# 16.net
KiCad netlist of a schematic drawn in EasyEDA Pro
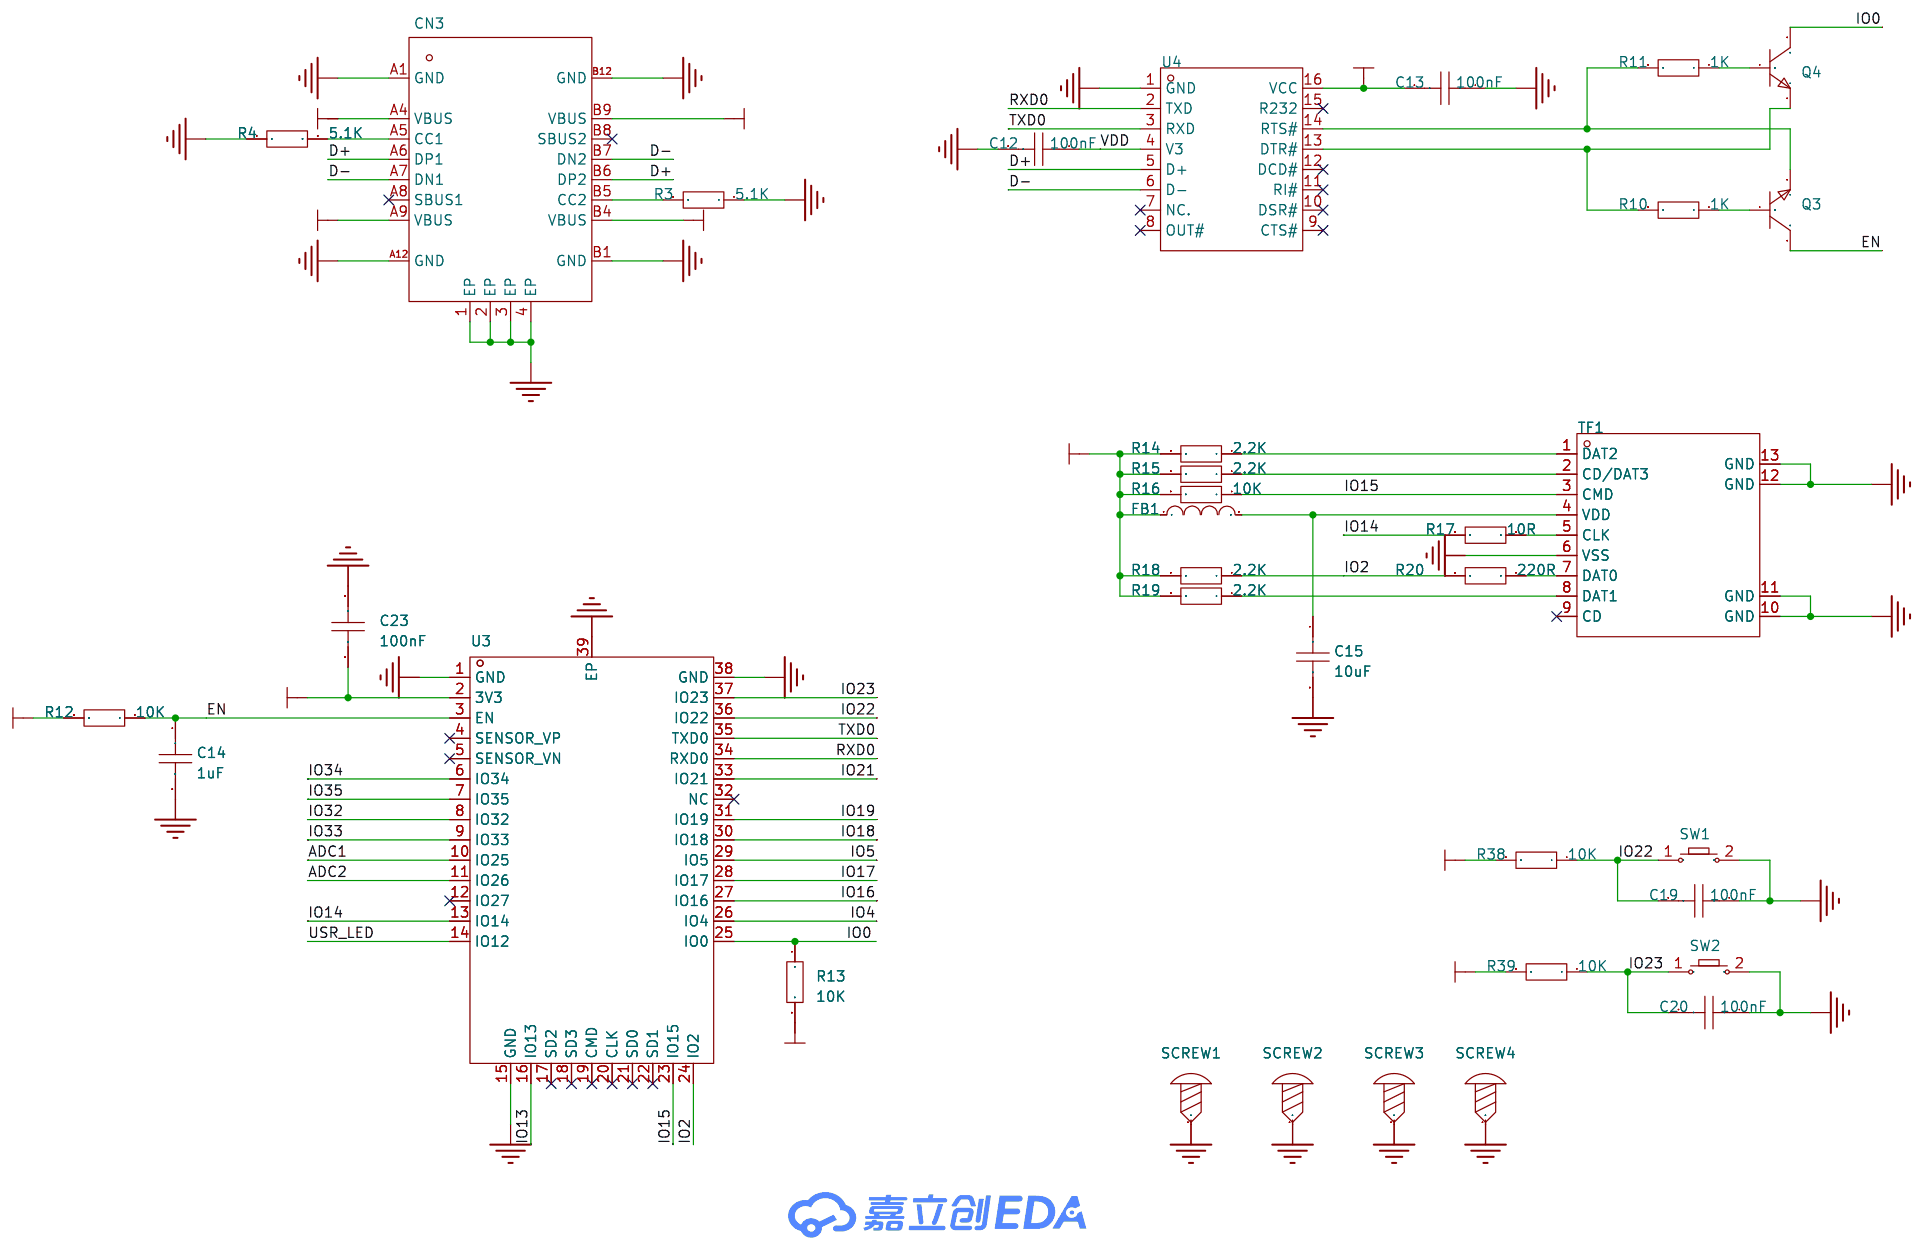
[diagram p0: ESP32]
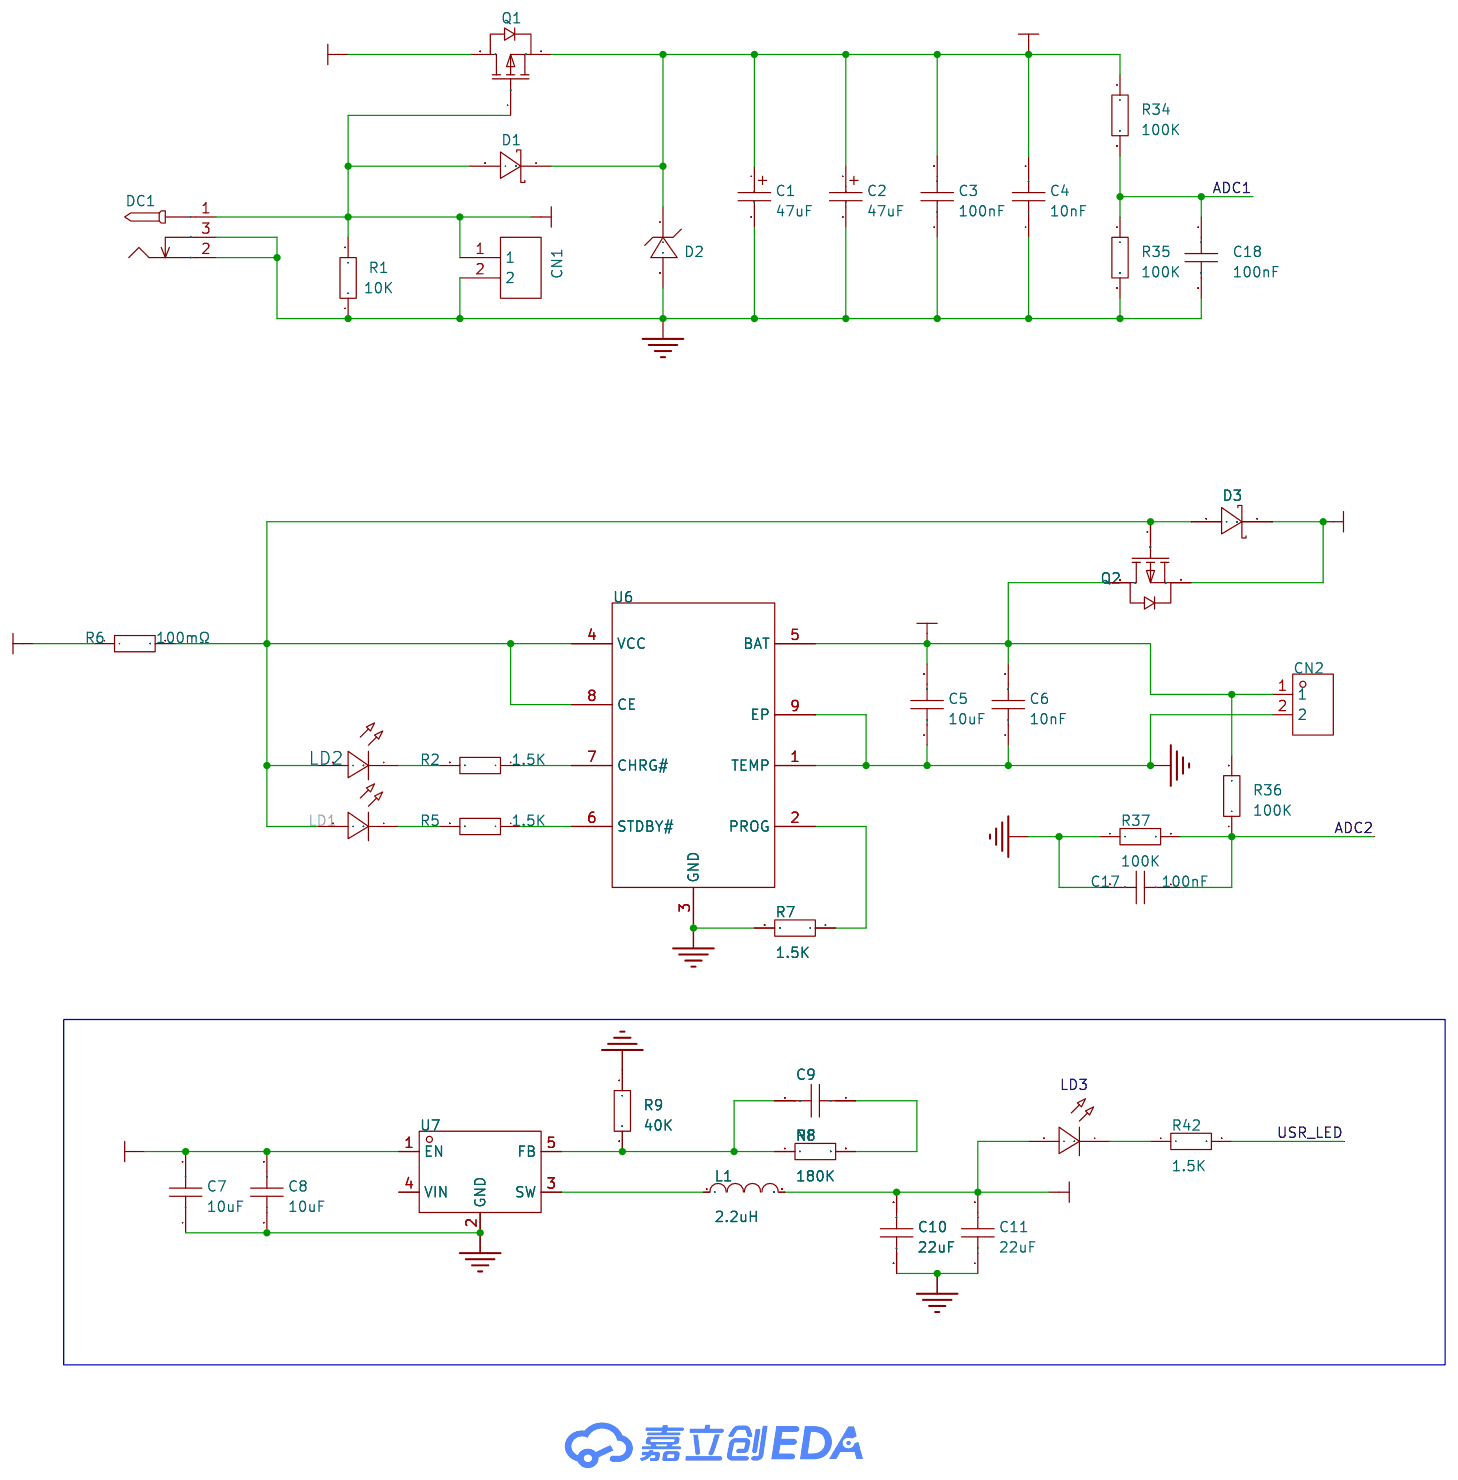
[diagram p1: DC]
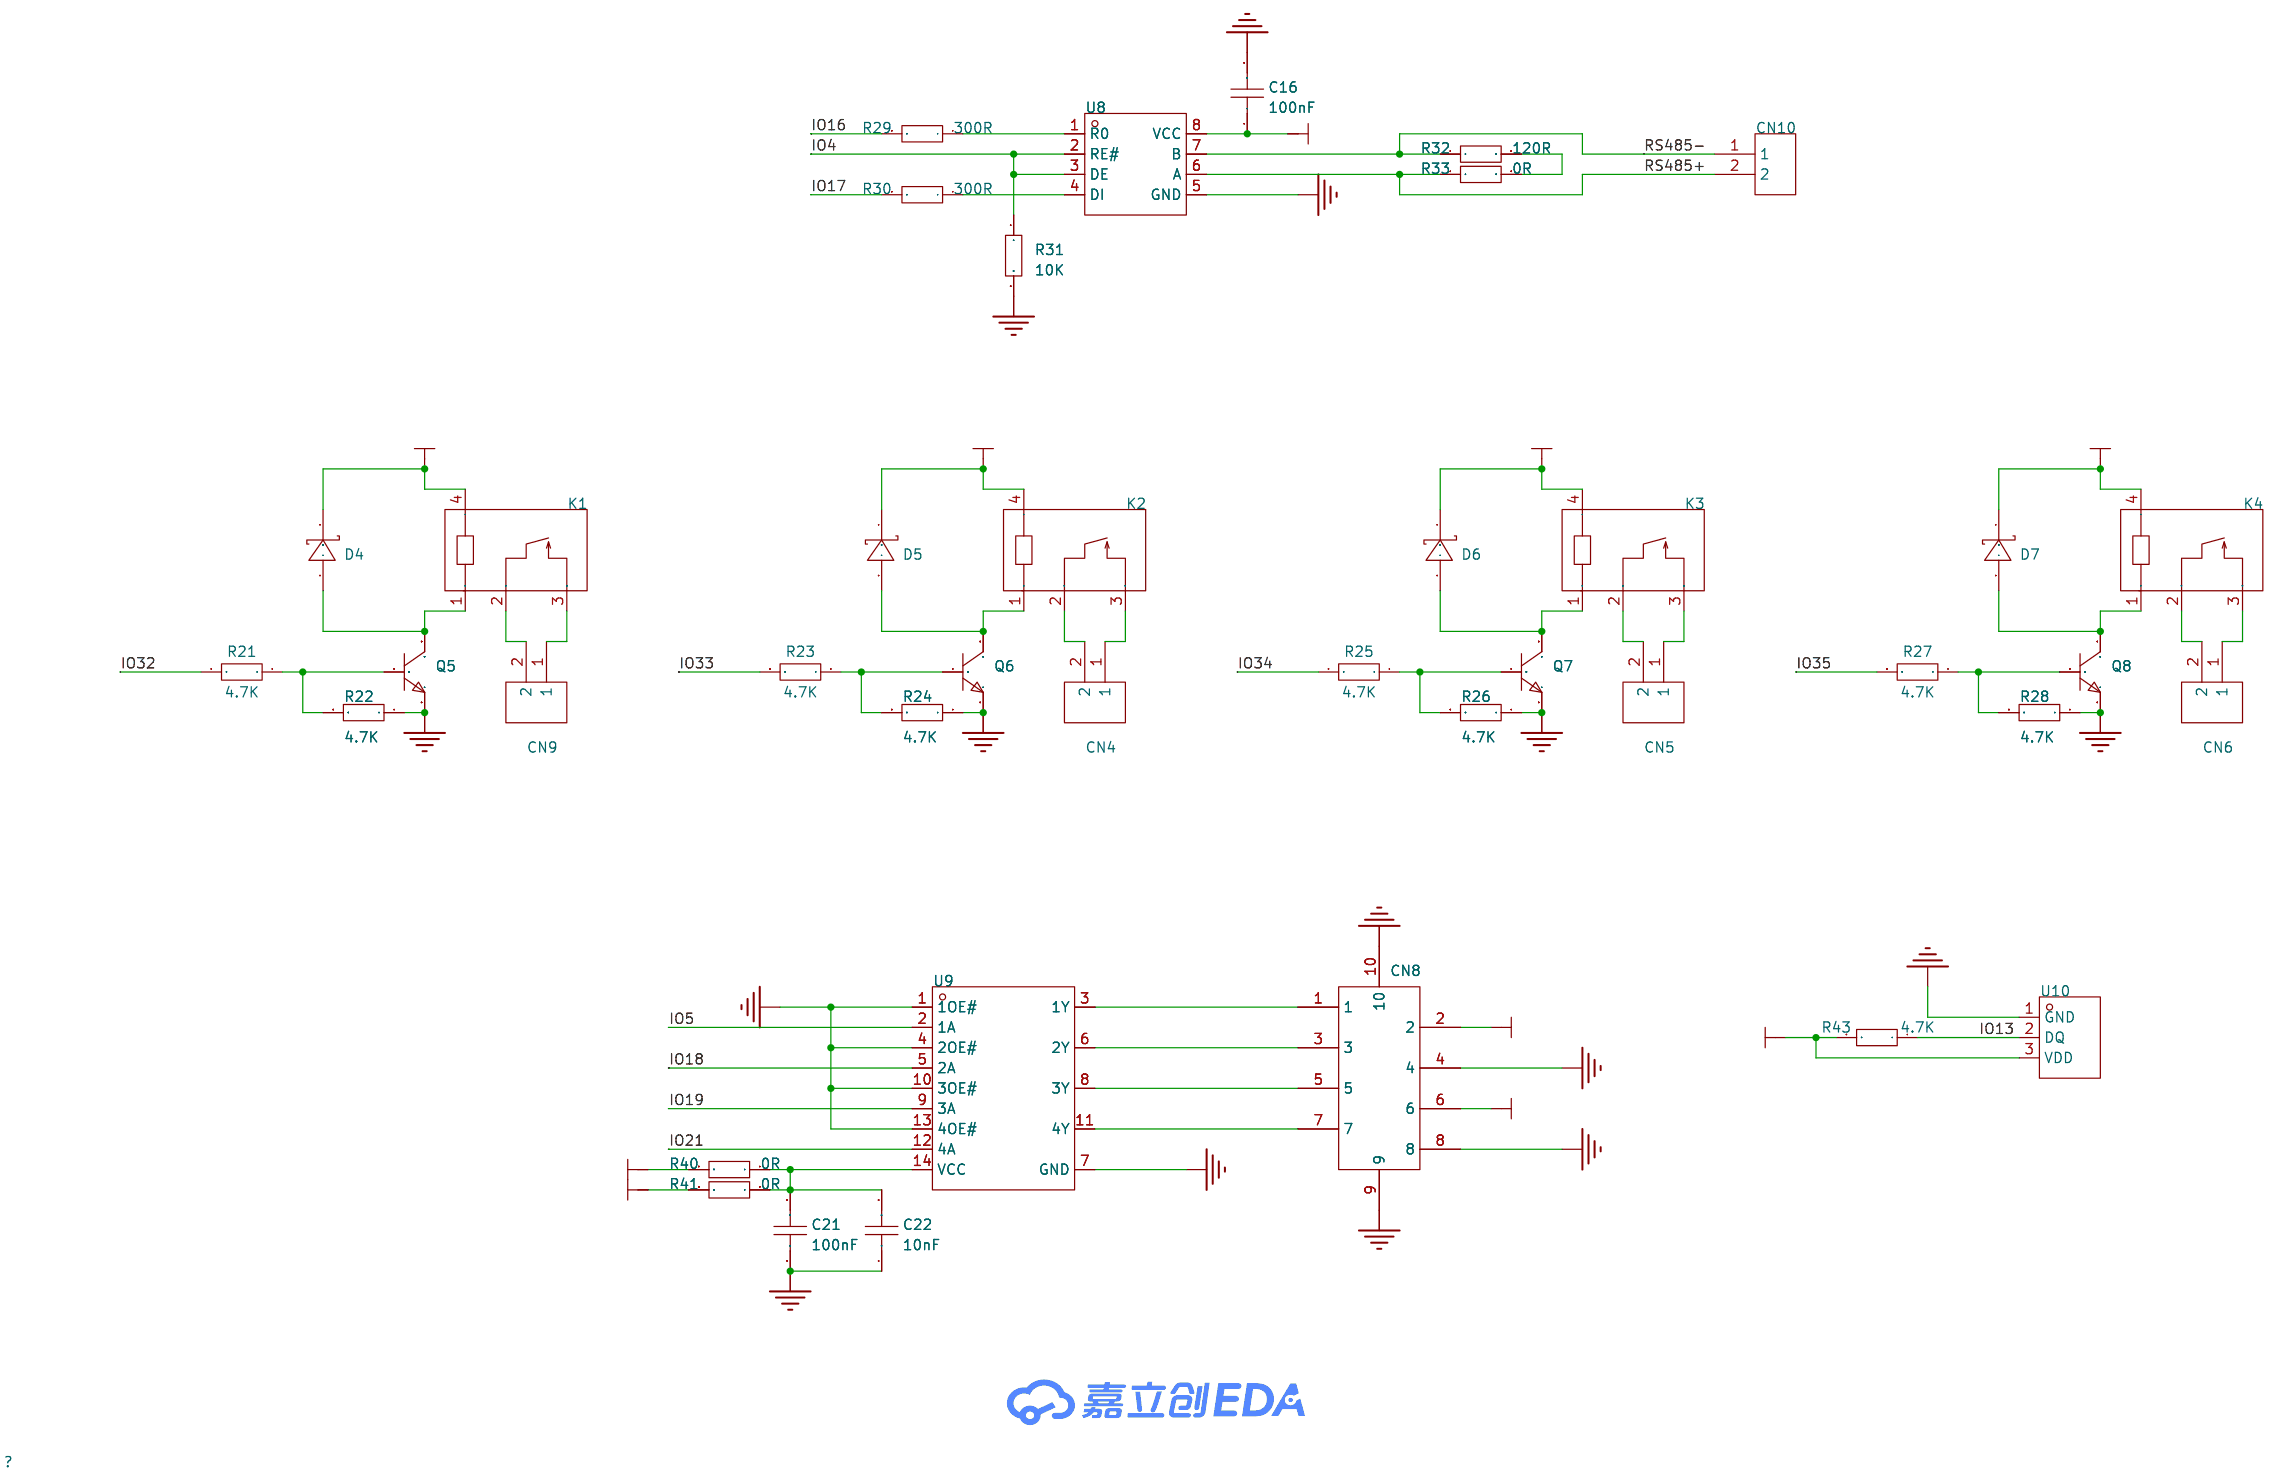
[diagram p2: RELAY]

(export (version "E")
  (design (tool "Eeschema 10.0.6"))
  (components
    (comp (ref "C12")
      (value "100nF")
      (footprint "easyedapro:C0805")
      (libsource (lib "easyedapro") (part "CapAcitance"))
    )
    (comp (ref "C13")
      (value "100nF")
      (footprint "easyedapro:C0805")
      (libsource (lib "easyedapro") (part "CapAcitance"))
    )
    (comp (ref "C14")
      (value "1uF")
      (footprint "easyedapro:C0805")
      (libsource (lib "easyedapro") (part "CapAcitance"))
    )
    (comp (ref "C15")
      (value "10uF")
      (footprint "easyedapro:C0805")
      (libsource (lib "easyedapro") (part "CapAcitance"))
    )
    (comp (ref "C19")
      (value "100nF")
      (footprint "easyedapro:C0805")
      (libsource (lib "easyedapro") (part "CapAcitance"))
    )
    (comp (ref "C20")
      (value "100nF")
      (footprint "easyedapro:C0805")
      (libsource (lib "easyedapro") (part "CapAcitance"))
    )
    (comp (ref "C23")
      (value "100nF")
      (footprint "easyedapro:C0805")
      (libsource (lib "easyedapro") (part "CapAcitance"))
    )
    (comp (ref "CN3")
      (value "~")
      (footprint "easyedapro:USB_TYPE-C-16P")
      (libsource (lib "easyedapro") (part "USB_TYPE-C-16P"))
    )
    (comp (ref "FB1")
      (value "10uH")
      (footprint "easyedapro:L0805")
      (libsource (lib "easyedapro") (part "SDFL2012S100KTF"))
    )
    (comp (ref "Q3")
      (value "SS8050")
      (footprint "easyedapro:SOT-23-3_L2.9-W1.3-P1.90-LS2.4-BR")
      (fields (field (name "Manufacturer") "宏迦橙"))
      (libsource (lib "easyedapro") (part "SS8050_C7420370"))
    )
    (comp (ref "Q4")
      (value "SS8050")
      (footprint "easyedapro:SOT-23-3_L2.9-W1.3-P1.90-LS2.4-BR")
      (fields (field (name "Manufacturer") "宏迦橙"))
      (libsource (lib "easyedapro") (part "SS8050_C7420370"))
    )
    (comp (ref "R3") (value "5.1K") (footprint "easyedapro:R0805") (libsource (lib "easyedapro") (part "电阻")))
    (comp (ref "R4") (value "5.1K") (footprint "easyedapro:R0805") (libsource (lib "easyedapro") (part "电阻")))
    (comp (ref "R10") (value "1K") (footprint "easyedapro:R0805") (libsource (lib "easyedapro") (part "电阻")))
    (comp (ref "R11") (value "1K") (footprint "easyedapro:R0805") (libsource (lib "easyedapro") (part "电阻")))
    (comp (ref "R12") (value "10K") (footprint "easyedapro:R0805") (libsource (lib "easyedapro") (part "电阻")))
    (comp (ref "R13") (value "10K") (footprint "easyedapro:R0805") (libsource (lib "easyedapro") (part "电阻")))
    (comp (ref "R14")
      (value "2.2K")
      (footprint "easyedapro:R0805")
      (libsource (lib "easyedapro") (part "电阻"))
    )
    (comp (ref "R15")
      (value "2.2K")
      (footprint "easyedapro:R0805")
      (libsource (lib "easyedapro") (part "电阻"))
    )
    (comp (ref "R16") (value "10K") (footprint "easyedapro:R0805") (libsource (lib "easyedapro") (part "电阻")))
    (comp (ref "R17") (value "10R") (footprint "easyedapro:R0805") (libsource (lib "easyedapro") (part "电阻")))
    (comp (ref "R18")
      (value "2.2K")
      (footprint "easyedapro:R0805")
      (libsource (lib "easyedapro") (part "电阻"))
    )
    (comp (ref "R19")
      (value "2.2K")
      (footprint "easyedapro:R0805")
      (libsource (lib "easyedapro") (part "电阻"))
    )
    (comp (ref "R20")
      (value "220R")
      (footprint "easyedapro:R0805")
      (libsource (lib "easyedapro") (part "电阻"))
    )
    (comp (ref "R38") (value "10K") (footprint "easyedapro:R0805") (libsource (lib "easyedapro") (part "电阻")))
    (comp (ref "R39") (value "10K") (footprint "easyedapro:R0805") (libsource (lib "easyedapro") (part "电阻")))
    (comp (ref "SCREW1")
      (value "~")
      (footprint "easyedapro:M2螺丝")
      (libsource (lib "easyedapro") (part "螺丝孔"))
    )
    (comp (ref "SCREW2")
      (value "~")
      (footprint "easyedapro:M2螺丝")
      (libsource (lib "easyedapro") (part "螺丝孔"))
    )
    (comp (ref "SCREW3")
      (value "~")
      (footprint "easyedapro:M2螺丝")
      (libsource (lib "easyedapro") (part "螺丝孔"))
    )
    (comp (ref "SCREW4")
      (value "~")
      (footprint "easyedapro:M2螺丝")
      (libsource (lib "easyedapro") (part "螺丝孔"))
    )
    (comp (ref "SW1")
      (value "~")
      (footprint "easyedapro:Key_SMD_3x4x2")
      (libsource (lib "easyedapro") (part "轻触按键x2"))
    )
    (comp (ref "SW2")
      (value "~")
      (footprint "easyedapro:Key_SMD_3x4x2")
      (libsource (lib "easyedapro") (part "轻触按键x2"))
    )
    (comp (ref "TF1")
      (value "TF-CARD H1.8")
      (footprint "easyedapro:TF-SMD_TF-CARD-H1.8")
      (fields (field (name "Manufacturer") "SHOU HAN(首韩)"))
      (libsource (lib "easyedapro") (part "TF-CARD H1.8"))
    )
    (comp (ref "U3")
      (value "ESP32-WROOM-32")
      (footprint "easyedapro:WIFIM-SMD_ESP-WROOM-32")
      (fields (field (name "Manufacturer") "ESPRESSIF(乐鑫)"))
      (libsource (lib "easyedapro") (part "ESP-WROOM-32"))
    )
    (comp (ref "U4")
      (value "CH340C")
      (footprint "easyedapro:SOP-16_L10.0-W3.9-P1.27-LS6.0-BL")
      (fields (field (name "Manufacturer") "WCH(南京沁恒)"))
      (libsource (lib "easyedapro") (part "CH340C"))
    )
    (comp (ref "C1")
      (value "47uF")
      (footprint "easyedapro:C_Ele_SMD_5x5.4mm")
      (libsource (lib "easyedapro") (part "CAP"))
    )
    (comp (ref "C2")
      (value "47uF")
      (footprint "easyedapro:C_Ele_SMD_5x5.4mm")
      (libsource (lib "easyedapro") (part "CAP"))
    )
    (comp (ref "C3")
      (value "100nF")
      (footprint "easyedapro:C0805")
      (libsource (lib "easyedapro") (part "CapAcitance"))
    )
    (comp (ref "C4")
      (value "10nF")
      (footprint "easyedapro:C0805")
      (libsource (lib "easyedapro") (part "CapAcitance"))
    )
    (comp (ref "C5")
      (value "10uF")
      (footprint "easyedapro:C0805")
      (libsource (lib "easyedapro") (part "CapAcitance"))
    )
    (comp (ref "C6")
      (value "10nF")
      (footprint "easyedapro:C0805")
      (libsource (lib "easyedapro") (part "CapAcitance"))
    )
    (comp (ref "C7")
      (value "10uF")
      (footprint "easyedapro:C0805")
      (libsource (lib "easyedapro") (part "CapAcitance"))
    )
    (comp (ref "C8")
      (value "10uF")
      (footprint "easyedapro:C0805")
      (libsource (lib "easyedapro") (part "CapAcitance"))
    )
    (comp (ref "C9")
      (value "NF")
      (footprint "easyedapro:C0805")
      (libsource (lib "easyedapro") (part "CapAcitance"))
    )
    (comp (ref "C10")
      (value "22uF")
      (footprint "easyedapro:C0805")
      (libsource (lib "easyedapro") (part "CapAcitance"))
    )
    (comp (ref "C11")
      (value "22uF")
      (footprint "easyedapro:C0805")
      (libsource (lib "easyedapro") (part "CapAcitance"))
    )
    (comp (ref "C17")
      (value "100nF")
      (footprint "easyedapro:C0805")
      (libsource (lib "easyedapro") (part "CapAcitance"))
    )
    (comp (ref "C18")
      (value "100nF")
      (footprint "easyedapro:C0805")
      (libsource (lib "easyedapro") (part "CapAcitance"))
    )
    (comp (ref "CN1")
      (value "WJ500V-5.08-2P")
      (footprint "easyedapro:CONN-TH_2P-P5.00_WJ500V-5.08-2P")
      (fields (field (name "Manufacturer") "KANGNEX(康奈克斯电气)"))
      (libsource (lib "easyedapro") (part "WJ500V-5.08-2P-14-00A"))
    )
    (comp (ref "CN2")
      (value "ZX-XH2.54-2PZZ")
      (footprint "easyedapro:CONN-TH_2P-P2.50_HX25003-2A")
      (fields (field (name "Manufacturer") "Megastar(兆星)"))
      (libsource (lib "easyedapro") (part "ZX-XH2.54-2PZZ"))
    )
    (comp (ref "D1")
      (value "SS34")
      (footprint "easyedapro:SMC_L6.9-W5.9-LS7.9-RD")
      (fields (field (name "Manufacturer") "onsemi(安森美)"))
      (libsource (lib "easyedapro") (part "SS34_C154551"))
    )
    (comp (ref "D2")
      (value "SMBJ6.0A")
      (footprint "easyedapro:SMB_L4.6-W3.6-LS5.3-RD")
      (fields (field (name "Manufacturer") "RUILON(瑞隆源)"))
      (libsource (lib "easyedapro") (part "SMBJ6.0A_C2987966"))
    )
    (comp (ref "D3")
      (value "SS34")
      (footprint "easyedapro:SMC_L6.9-W5.9-LS7.9-RD")
      (fields (field (name "Manufacturer") "onsemi(安森美)"))
      (libsource (lib "easyedapro") (part "SS34_C154551"))
    )
    (comp (ref "DC1")
      (value "~")
      (footprint "easyedapro:DC-005_2.5")
      (libsource (lib "easyedapro") (part "DC-005_2.5"))
    )
    (comp (ref "L1")
      (value "2.2uH")
      (footprint "easyedapro:IND-SMD_L4.4-W4.2")
      (fields (field (name "Manufacturer Part") "FXL0420-2R2-M") (field (name "Manufacturer") "cjiang(长江微电)"))
      (libsource (lib "easyedapro") (part "FXL0420-2R2-M"))
    )
    (comp (ref "LD1")
      (value "~")
      (footprint "easyedapro:LED_0805")
      (libsource (lib "easyedapro") (part "LED_G"))
    )
    (comp (ref "LD2")
      (value "~")
      (footprint "easyedapro:LED_0805")
      (libsource (lib "easyedapro") (part "LED_R"))
    )
    (comp (ref "LD3")
      (value "~")
      (footprint "easyedapro:LED_0805")
      (libsource (lib "easyedapro") (part "LED_B"))
    )
    (comp (ref "Q1")
      (value "AO3401A")
      (footprint "easyedapro:SOT-23_L2.9-W1.3-P1.90-LS2.4-BR")
      (fields (field (name "Manufacturer") "AOS"))
      (libsource (lib "easyedapro") (part "AO3401A"))
    )
    (comp (ref "Q2")
      (value "AO3401A")
      (footprint "easyedapro:SOT-23_L2.9-W1.3-P1.90-LS2.4-BR")
      (fields (field (name "Manufacturer") "AOS"))
      (libsource (lib "easyedapro") (part "AO3401A"))
    )
    (comp (ref "R1") (value "10K") (footprint "easyedapro:R0805") (libsource (lib "easyedapro") (part "电阻")))
    (comp (ref "R2") (value "1.5K") (footprint "easyedapro:R0805") (libsource (lib "easyedapro") (part "电阻")))
    (comp (ref "R5") (value "1.5K") (footprint "easyedapro:R0805") (libsource (lib "easyedapro") (part "电阻")))
    (comp (ref "R6")
      (value "100mΩ")
      (footprint "easyedapro:R1210")
      (fields
        (field (name "Manufacturer Part") "1210W2F100LT5E")
        (field (name "Manufacturer") "UNI-ROYAL(厚声)")
      )
      (libsource (lib "easyedapro") (part "1210W2F100LT5E"))
    )
    (comp (ref "R7") (value "1.5K") (footprint "easyedapro:R0805") (libsource (lib "easyedapro") (part "电阻")))
    (comp (ref "R8") (value "180K") (footprint "easyedapro:R0805") (libsource (lib "easyedapro") (part "电阻")))
    (comp (ref "R9") (value "40K") (footprint "easyedapro:R0805") (libsource (lib "easyedapro") (part "电阻")))
    (comp (ref "R34")
      (value "100K")
      (footprint "easyedapro:R0805")
      (libsource (lib "easyedapro") (part "电阻"))
    )
    (comp (ref "R35")
      (value "100K")
      (footprint "easyedapro:R0805")
      (libsource (lib "easyedapro") (part "电阻"))
    )
    (comp (ref "R36")
      (value "100K")
      (footprint "easyedapro:R0805")
      (libsource (lib "easyedapro") (part "电阻"))
    )
    (comp (ref "R37")
      (value "100K")
      (footprint "easyedapro:R0805")
      (libsource (lib "easyedapro") (part "电阻"))
    )
    (comp (ref "R42")
      (value "1.5K")
      (footprint "easyedapro:R0805")
      (libsource (lib "easyedapro") (part "电阻"))
    )
    (comp (ref "U6")
      (value "TP4056-42-ESOP8")
      (footprint "easyedapro:ESOP-8_L4.9-W3.9-P1.27-LS6.0-BL-EP")
      (fields (field (name "Manufacturer") "TOPPOWER(南京拓微)"))
      (libsource (lib "easyedapro") (part "TP4056"))
    )
    (comp (ref "U7") (value "~") (libsource (lib "easyedapro") (part "XDC")))
    (comp (ref "C16")
      (value "100nF")
      (footprint "easyedapro:C0805")
      (libsource (lib "easyedapro") (part "CapAcitance"))
    )
    (comp (ref "C21")
      (value "100nF")
      (footprint "easyedapro:C0805")
      (libsource (lib "easyedapro") (part "CapAcitance"))
    )
    (comp (ref "C22")
      (value "10nF")
      (footprint "easyedapro:C0805")
      (libsource (lib "easyedapro") (part "CapAcitance"))
    )
    (comp (ref "CN4")
      (value "WJ500V-5.08-2P")
      (footprint "easyedapro:CONN-TH_2P-P5.00_WJ500V-5.08-2P")
      (fields (field (name "Manufacturer") "KANGNEX(康奈克斯电气)"))
      (libsource (lib "easyedapro") (part "WJ500V-5.08-2P-14-00A"))
    )
    (comp (ref "CN5")
      (value "WJ500V-5.08-2P")
      (footprint "easyedapro:CONN-TH_2P-P5.00_WJ500V-5.08-2P")
      (fields (field (name "Manufacturer") "KANGNEX(康奈克斯电气)"))
      (libsource (lib "easyedapro") (part "WJ500V-5.08-2P-14-00A"))
    )
    (comp (ref "CN6")
      (value "WJ500V-5.08-2P")
      (footprint "easyedapro:CONN-TH_2P-P5.00_WJ500V-5.08-2P")
      (fields (field (name "Manufacturer") "KANGNEX(康奈克斯电气)"))
      (libsource (lib "easyedapro") (part "WJ500V-5.08-2P-14-00A"))
    )
    (comp (ref "CN8")
      (value "8P-立贴带锁")
      (footprint "easyedapro:FPC-SMD_8P-P0.50_AFC11-S08ICC-00")
      (libsource (lib "easyedapro") (part "8P-立贴带锁"))
    )
    (comp (ref "CN9")
      (value "WJ500V-5.08-2P")
      (footprint "easyedapro:CONN-TH_2P-P5.00_WJ500V-5.08-2P")
      (fields (field (name "Manufacturer") "KANGNEX(康奈克斯电气)"))
      (libsource (lib "easyedapro") (part "WJ500V-5.08-2P-14-00A"))
    )
    (comp (ref "CN10")
      (value "WJ500V-5.08-2P")
      (footprint "easyedapro:CONN-TH_2P-P5.00_WJ500V-5.08-2P")
      (fields (field (name "Manufacturer") "KANGNEX(康奈克斯电气)"))
      (libsource (lib "easyedapro") (part "WJ500V-5.08-2P-14-00A"))
    )
    (comp (ref "D4")
      (value "SS34")
      (footprint "easyedapro:SMC_L6.9-W5.9-LS7.9-RD")
      (fields (field (name "Manufacturer") "onsemi(安森美)"))
      (libsource (lib "easyedapro") (part "SS34_C154551"))
    )
    (comp (ref "D5")
      (value "SS34")
      (footprint "easyedapro:SMC_L6.9-W5.9-LS7.9-RD")
      (fields (field (name "Manufacturer") "onsemi(安森美)"))
      (libsource (lib "easyedapro") (part "SS34_C154551"))
    )
    (comp (ref "D6")
      (value "SS34")
      (footprint "easyedapro:SMC_L6.9-W5.9-LS7.9-RD")
      (fields (field (name "Manufacturer") "onsemi(安森美)"))
      (libsource (lib "easyedapro") (part "SS34_C154551"))
    )
    (comp (ref "D7")
      (value "SS34")
      (footprint "easyedapro:SMC_L6.9-W5.9-LS7.9-RD")
      (fields (field (name "Manufacturer") "onsemi(安森美)"))
      (libsource (lib "easyedapro") (part "SS34_C154551"))
    )
    (comp (ref "K1")
      (value "G5NB-1A-E-12VDC")
      (footprint "easyedapro:RELAY-TH_G5NB-1A-E-DCXX")
      (libsource (lib "easyedapro") (part "G5NB-1A-E-12VDC"))
    )
    (comp (ref "K2")
      (value "G5NB-1A-E-12VDC")
      (footprint "easyedapro:RELAY-TH_G5NB-1A-E-DCXX")
      (libsource (lib "easyedapro") (part "G5NB-1A-E-12VDC"))
    )
    (comp (ref "K3")
      (value "G5NB-1A-E-12VDC")
      (footprint "easyedapro:RELAY-TH_G5NB-1A-E-DCXX")
      (libsource (lib "easyedapro") (part "G5NB-1A-E-12VDC"))
    )
    (comp (ref "K4")
      (value "G5NB-1A-E-12VDC")
      (footprint "easyedapro:RELAY-TH_G5NB-1A-E-DCXX")
      (libsource (lib "easyedapro") (part "G5NB-1A-E-12VDC"))
    )
    (comp (ref "Q5")
      (value "SS8050")
      (footprint "easyedapro:SOT-23-3_L2.9-W1.3-P1.90-LS2.4-BR")
      (fields (field (name "Manufacturer") "宏迦橙"))
      (libsource (lib "easyedapro") (part "SS8050_C7420370"))
    )
    (comp (ref "Q6")
      (value "SS8050")
      (footprint "easyedapro:SOT-23-3_L2.9-W1.3-P1.90-LS2.4-BR")
      (fields (field (name "Manufacturer") "宏迦橙"))
      (libsource (lib "easyedapro") (part "SS8050_C7420370"))
    )
    (comp (ref "Q7")
      (value "SS8050")
      (footprint "easyedapro:SOT-23-3_L2.9-W1.3-P1.90-LS2.4-BR")
      (fields (field (name "Manufacturer") "宏迦橙"))
      (libsource (lib "easyedapro") (part "SS8050_C7420370"))
    )
    (comp (ref "Q8")
      (value "SS8050")
      (footprint "easyedapro:SOT-23-3_L2.9-W1.3-P1.90-LS2.4-BR")
      (fields (field (name "Manufacturer") "宏迦橙"))
      (libsource (lib "easyedapro") (part "SS8050_C7420370"))
    )
    (comp (ref "R21")
      (value "4.7K")
      (footprint "easyedapro:R0805")
      (libsource (lib "easyedapro") (part "电阻"))
    )
    (comp (ref "R22")
      (value "4.7K")
      (footprint "easyedapro:R0805")
      (libsource (lib "easyedapro") (part "电阻"))
    )
    (comp (ref "R23")
      (value "4.7K")
      (footprint "easyedapro:R0805")
      (libsource (lib "easyedapro") (part "电阻"))
    )
    (comp (ref "R24")
      (value "4.7K")
      (footprint "easyedapro:R0805")
      (libsource (lib "easyedapro") (part "电阻"))
    )
    (comp (ref "R25")
      (value "4.7K")
      (footprint "easyedapro:R0805")
      (libsource (lib "easyedapro") (part "电阻"))
    )
    (comp (ref "R26")
      (value "4.7K")
      (footprint "easyedapro:R0805")
      (libsource (lib "easyedapro") (part "电阻"))
    )
    (comp (ref "R27")
      (value "4.7K")
      (footprint "easyedapro:R0805")
      (libsource (lib "easyedapro") (part "电阻"))
    )
    (comp (ref "R28")
      (value "4.7K")
      (footprint "easyedapro:R0805")
      (libsource (lib "easyedapro") (part "电阻"))
    )
    (comp (ref "R29")
      (value "300R")
      (footprint "easyedapro:R0805")
      (libsource (lib "easyedapro") (part "电阻"))
    )
    (comp (ref "R30")
      (value "300R")
      (footprint "easyedapro:R0805")
      (libsource (lib "easyedapro") (part "电阻"))
    )
    (comp (ref "R31") (value "10K") (footprint "easyedapro:R0805") (libsource (lib "easyedapro") (part "电阻")))
    (comp (ref "R32")
      (value "120R")
      (footprint "easyedapro:R0805")
      (libsource (lib "easyedapro") (part "电阻"))
    )
    (comp (ref "R33") (value "0R") (footprint "easyedapro:R0805") (libsource (lib "easyedapro") (part "电阻")))
    (comp (ref "R40") (value "0R") (footprint "easyedapro:R0805") (libsource (lib "easyedapro") (part "电阻")))
    (comp (ref "R41") (value "0R") (footprint "easyedapro:R0805") (libsource (lib "easyedapro") (part "电阻")))
    (comp (ref "R43")
      (value "4.7K")
      (footprint "easyedapro:R0805")
      (libsource (lib "easyedapro") (part "电阻"))
    )
    (comp (ref "U8")
      (value "MAX485EIM/TR")
      (footprint "easyedapro:SOP-8_L4.9-W3.9-P1.27-LS6.0-BL")
      (fields (field (name "Manufacturer") "HGSEMI(华冠)"))
      (libsource (lib "easyedapro") (part "MAX485EIM/TR"))
    )
    (comp (ref "U9")
      (value "74HC125D/S400118")
      (footprint "easyedapro:SOIC-14_L8.6-W3.8-P1.27-LS6.0-BL")
      (fields (field (name "Manufacturer") "Nexperia(安世)"))
      (libsource (lib "easyedapro") (part "74HC125D/S400118"))
    )
    (comp (ref "U10")
      (value "GX18B20")
      (footprint "easyedapro:TO-92-3_L4.9-W3.7-P1.27-L")
      (fields (field (name "Manufacturer") "GXCAS(中科银河芯)"))
      (libsource (lib "easyedapro") (part "GX18B20"))
    )
  )
  (nets
    (net (code "1") (name "ADC1") (class "Default")
      (node (ref "C18") (pin "1") (pinfunction "1_1") (pintype "input"))
      (node (ref "R34") (pin "2") (pinfunction "2_2") (pintype "input"))
      (node (ref "R35") (pin "1") (pinfunction "1_1") (pintype "input"))
      (node (ref "U3") (pin "10") (pinfunction "IO25_10") (pintype "unspecified"))
    )
    (net (code "2") (name "ADC2") (class "Default")
      (node (ref "C17") (pin "1") (pinfunction "1_1") (pintype "input"))
      (node (ref "R36") (pin "1") (pinfunction "1_1") (pintype "input"))
      (node (ref "R37") (pin "2") (pinfunction "2_2") (pintype "input"))
      (node (ref "U3") (pin "11") (pinfunction "IO26_11") (pintype "unspecified"))
    )
    (net (code "3") (name "D+") (class "Default")
      (node (ref "CN3") (pin "A6") (pinfunction "DP1_A6") (pintype "input"))
      (node (ref "CN3") (pin "B6") (pinfunction "DP2_B6") (pintype "input"))
      (node (ref "U4") (pin "5") (pinfunction "D+_5") (pintype "unspecified"))
    )
    (net (code "4") (name "D-") (class "Default")
      (node (ref "CN3") (pin "A7") (pinfunction "DN1_A7") (pintype "input"))
      (node (ref "CN3") (pin "B7") (pinfunction "DN2_B7") (pintype "input"))
      (node (ref "U4") (pin "6") (pinfunction "D-_6") (pintype "unspecified"))
    )
    (net (code "5") (name "EN") (class "Default")
      (node (ref "C14") (pin "1") (pinfunction "1_1") (pintype "input"))
      (node (ref "Q3") (pin "3") (pinfunction "C_3") (pintype "input"))
      (node (ref "R12") (pin "1") (pinfunction "1_1") (pintype "input"))
      (node (ref "U3") (pin "3") (pinfunction "EN_3") (pintype "unspecified"))
    )
    (net (code "6") (name "GND") (class "Default")
      (node (ref "C1") (pin "2") (pinfunction "2_2") (pintype "input"))
      (node (ref "C10") (pin "1") (pinfunction "1_1") (pintype "input"))
      (node (ref "C11") (pin "1") (pinfunction "1_1") (pintype "input"))
      (node (ref "C12") (pin "2") (pinfunction "2_2") (pintype "input"))
      (node (ref "C13") (pin "1") (pinfunction "1_1") (pintype "input"))
      (node (ref "C14") (pin "2") (pinfunction "2_2") (pintype "input"))
      (node (ref "C15") (pin "2") (pinfunction "2_2") (pintype "input"))
      (node (ref "C16") (pin "2") (pinfunction "2_2") (pintype "input"))
      (node (ref "C17") (pin "2") (pinfunction "2_2") (pintype "input"))
      (node (ref "C18") (pin "2") (pinfunction "2_2") (pintype "input"))
      (node (ref "C19") (pin "1") (pinfunction "1_1") (pintype "input"))
      (node (ref "C2") (pin "2") (pinfunction "2_2") (pintype "input"))
      (node (ref "C20") (pin "1") (pinfunction "1_1") (pintype "input"))
      (node (ref "C21") (pin "1") (pinfunction "1_1") (pintype "input"))
      (node (ref "C22") (pin "1") (pinfunction "1_1") (pintype "input"))
      (node (ref "C23") (pin "2") (pinfunction "2_2") (pintype "input"))
      (node (ref "C3") (pin "1") (pinfunction "1_1") (pintype "input"))
      (node (ref "C4") (pin "1") (pinfunction "1_1") (pintype "input"))
      (node (ref "C5") (pin "1") (pinfunction "1_1") (pintype "input"))
      (node (ref "C6") (pin "1") (pinfunction "1_1") (pintype "input"))
      (node (ref "C7") (pin "1") (pinfunction "1_1") (pintype "input"))
      (node (ref "C8") (pin "1") (pinfunction "1_1") (pintype "input"))
      (node (ref "CN1") (pin "2") (pinfunction "2_2") (pintype "unspecified"))
      (node (ref "CN2") (pin "2") (pinfunction "2_2") (pintype "unspecified"))
      (node (ref "CN3") (pin "1") (pinfunction "EP_1") (pintype "input"))
      (node (ref "CN3") (pin "2") (pinfunction "EP_2") (pintype "input"))
      (node (ref "CN3") (pin "3") (pinfunction "EP_3") (pintype "input"))
      (node (ref "CN3") (pin "4") (pinfunction "EP_4") (pintype "input"))
      (node (ref "CN3") (pin "A1") (pinfunction "GND_A1") (pintype "input"))
      (node (ref "CN3") (pin "A12") (pinfunction "GND_A12") (pintype "input"))
      (node (ref "CN3") (pin "B1") (pinfunction "GND_B1") (pintype "input"))
      (node (ref "CN3") (pin "B12") (pinfunction "GND_B12") (pintype "input"))
      (node (ref "CN8") (pin "10") (pinfunction "10_10") (pintype "unspecified"))
      (node (ref "CN8") (pin "4") (pinfunction "4_4") (pintype "unspecified"))
      (node (ref "CN8") (pin "8") (pinfunction "8_8") (pintype "unspecified"))
      (node (ref "CN8") (pin "9") (pinfunction "9_9") (pintype "unspecified"))
      (node (ref "D2") (pin "2") (pinfunction "2_2") (pintype "unspecified"))
      (node (ref "DC1") (pin "2") (pinfunction "2_2") (pintype "input"))
      (node (ref "DC1") (pin "3") (pinfunction "3_3") (pintype "input"))
      (node (ref "Q5") (pin "2") (pinfunction "E_2") (pintype "input"))
      (node (ref "Q6") (pin "2") (pinfunction "E_2") (pintype "input"))
      (node (ref "Q7") (pin "2") (pinfunction "E_2") (pintype "input"))
      (node (ref "Q8") (pin "2") (pinfunction "E_2") (pintype "input"))
      (node (ref "R1") (pin "1") (pinfunction "1_1") (pintype "input"))
      (node (ref "R22") (pin "1") (pinfunction "1_1") (pintype "input"))
      (node (ref "R24") (pin "1") (pinfunction "1_1") (pintype "input"))
      (node (ref "R26") (pin "1") (pinfunction "1_1") (pintype "input"))
      (node (ref "R28") (pin "1") (pinfunction "1_1") (pintype "input"))
      (node (ref "R3") (pin "1") (pinfunction "1_1") (pintype "input"))
      (node (ref "R31") (pin "2") (pinfunction "2_2") (pintype "input"))
      (node (ref "R35") (pin "2") (pinfunction "2_2") (pintype "input"))
      (node (ref "R37") (pin "1") (pinfunction "1_1") (pintype "input"))
      (node (ref "R4") (pin "1") (pinfunction "1_1") (pintype "input"))
      (node (ref "R7") (pin "2") (pinfunction "2_2") (pintype "input"))
      (node (ref "R9") (pin "1") (pinfunction "1_1") (pintype "input"))
      (node (ref "SCREW1") (pin "1") (pinfunction "1_1") (pintype "input"))
      (node (ref "SCREW2") (pin "1") (pinfunction "1_1") (pintype "input"))
      (node (ref "SCREW3") (pin "1") (pinfunction "1_1") (pintype "input"))
      (node (ref "SCREW4") (pin "1") (pinfunction "1_1") (pintype "input"))
      (node (ref "SW1") (pin "2") (pinfunction "2_2") (pintype "input"))
      (node (ref "SW2") (pin "2") (pinfunction "2_2") (pintype "input"))
      (node (ref "TF1") (pin "10") (pinfunction "GND_10") (pintype "unspecified"))
      (node (ref "TF1") (pin "11") (pinfunction "GND_11") (pintype "unspecified"))
      (node (ref "TF1") (pin "12") (pinfunction "GND_12") (pintype "unspecified"))
      (node (ref "TF1") (pin "13") (pinfunction "GND_13") (pintype "unspecified"))
      (node (ref "TF1") (pin "6") (pinfunction "VSS_6") (pintype "unspecified"))
      (node (ref "U10") (pin "1") (pinfunction "GND_1") (pintype "input"))
      (node (ref "U3") (pin "1") (pinfunction "GND_1") (pintype "unspecified"))
      (node (ref "U3") (pin "15") (pinfunction "GND_15") (pintype "unspecified"))
      (node (ref "U3") (pin "38") (pinfunction "GND_38") (pintype "unspecified"))
      (node (ref "U3") (pin "39") (pinfunction "EP_39") (pintype "unspecified"))
      (node (ref "U4") (pin "1") (pinfunction "GND_1") (pintype "unspecified"))
      (node (ref "U6") (pin "1") (pinfunction "TEMP_1") (pintype "unspecified"))
      (node (ref "U6") (pin "3") (pinfunction "GND_3") (pintype "unspecified"))
      (node (ref "U6") (pin "9") (pinfunction "EP_9") (pintype "unspecified"))
      (node (ref "U7") (pin "2") (pinfunction "GND_2") (pintype "input"))
      (node (ref "U8") (pin "5") (pinfunction "GND_5") (pintype "unspecified"))
      (node (ref "U9") (pin "1") (pinfunction "1OE#_1") (pintype "unspecified"))
      (node (ref "U9") (pin "10") (pinfunction "3OE#_10") (pintype "unspecified"))
      (node (ref "U9") (pin "13") (pinfunction "4OE#_13") (pintype "unspecified"))
      (node (ref "U9") (pin "4") (pinfunction "2OE#_4") (pintype "unspecified"))
      (node (ref "U9") (pin "7") (pinfunction "GND_7") (pintype "unspecified"))
    )
    (net (code "7") (name "IO0") (class "Default")
      (node (ref "Q4") (pin "3") (pinfunction "C_3") (pintype "input"))
      (node (ref "R13") (pin "1") (pinfunction "1_1") (pintype "input"))
      (node (ref "U3") (pin "25") (pinfunction "IO0_25") (pintype "unspecified"))
    )
    (net (code "8") (name "IO2") (class "Default")
      (node (ref "R18") (pin "1") (pinfunction "1_1") (pintype "input"))
      (node (ref "R20") (pin "2") (pinfunction "2_2") (pintype "input"))
      (node (ref "U3") (pin "24") (pinfunction "IO2_24") (pintype "unspecified"))
    )
    (net (code "9") (name "IO4") (class "Default")
      (node (ref "R31") (pin "1") (pinfunction "1_1") (pintype "input"))
      (node (ref "U3") (pin "26") (pinfunction "IO4_26") (pintype "unspecified"))
      (node (ref "U8") (pin "2") (pinfunction "RE#_2") (pintype "unspecified"))
      (node (ref "U8") (pin "3") (pinfunction "DE_3") (pintype "unspecified"))
    )
    (net (code "10") (name "IO5") (class "Default")
      (node (ref "U3") (pin "29") (pinfunction "IO5_29") (pintype "unspecified"))
      (node (ref "U9") (pin "2") (pinfunction "1A_2") (pintype "unspecified"))
    )
    (net (code "11") (name "IO13") (class "Default")
      (node (ref "R43") (pin "1") (pinfunction "1_1") (pintype "input"))
      (node (ref "U10") (pin "2") (pinfunction "DQ_2") (pintype "input"))
      (node (ref "U3") (pin "16") (pinfunction "IO13_16") (pintype "unspecified"))
    )
    (net (code "12") (name "IO14") (class "Default")
      (node (ref "R17") (pin "2") (pinfunction "2_2") (pintype "input"))
      (node (ref "U3") (pin "13") (pinfunction "IO14_13") (pintype "unspecified"))
    )
    (net (code "13") (name "IO15") (class "Default")
      (node (ref "R16") (pin "1") (pinfunction "1_1") (pintype "input"))
      (node (ref "TF1") (pin "3") (pinfunction "CMD_3") (pintype "unspecified"))
      (node (ref "U3") (pin "23") (pinfunction "IO15_23") (pintype "unspecified"))
    )
    (net (code "14") (name "IO16") (class "Default")
      (node (ref "R29") (pin "2") (pinfunction "2_2") (pintype "input"))
      (node (ref "U3") (pin "27") (pinfunction "IO16_27") (pintype "unspecified"))
    )
    (net (code "15") (name "IO17") (class "Default")
      (node (ref "R30") (pin "2") (pinfunction "2_2") (pintype "input"))
      (node (ref "U3") (pin "28") (pinfunction "IO17_28") (pintype "unspecified"))
    )
    (net (code "16") (name "IO18") (class "Default")
      (node (ref "U3") (pin "30") (pinfunction "IO18_30") (pintype "unspecified"))
      (node (ref "U9") (pin "5") (pinfunction "2A_5") (pintype "unspecified"))
    )
    (net (code "17") (name "IO19") (class "Default")
      (node (ref "U3") (pin "31") (pinfunction "IO19_31") (pintype "unspecified"))
      (node (ref "U9") (pin "9") (pinfunction "3A_9") (pintype "unspecified"))
    )
    (net (code "18") (name "IO21") (class "Default")
      (node (ref "U3") (pin "33") (pinfunction "IO21_33") (pintype "unspecified"))
      (node (ref "U9") (pin "12") (pinfunction "4A_12") (pintype "unspecified"))
    )
    (net (code "19") (name "IO22") (class "Default")
      (node (ref "C19") (pin "2") (pinfunction "2_2") (pintype "input"))
      (node (ref "R38") (pin "1") (pinfunction "1_1") (pintype "input"))
      (node (ref "SW1") (pin "1") (pinfunction "1_1") (pintype "input"))
      (node (ref "U3") (pin "36") (pinfunction "IO22_36") (pintype "unspecified"))
    )
    (net (code "20") (name "IO23") (class "Default")
      (node (ref "C20") (pin "2") (pinfunction "2_2") (pintype "input"))
      (node (ref "R39") (pin "1") (pinfunction "1_1") (pintype "input"))
      (node (ref "SW2") (pin "1") (pinfunction "1_1") (pintype "input"))
      (node (ref "U3") (pin "37") (pinfunction "IO23_37") (pintype "unspecified"))
    )
    (net (code "21") (name "IO32") (class "Default")
      (node (ref "R21") (pin "2") (pinfunction "2_2") (pintype "input"))
      (node (ref "U3") (pin "8") (pinfunction "IO32_8") (pintype "unspecified"))
    )
    (net (code "22") (name "IO33") (class "Default")
      (node (ref "R23") (pin "2") (pinfunction "2_2") (pintype "input"))
      (node (ref "U3") (pin "9") (pinfunction "IO33_9") (pintype "unspecified"))
    )
    (net (code "23") (name "IO34") (class "Default")
      (node (ref "R25") (pin "2") (pinfunction "2_2") (pintype "input"))
      (node (ref "U3") (pin "6") (pinfunction "IO34_6") (pintype "unspecified"))
    )
    (net (code "24") (name "IO35") (class "Default")
      (node (ref "R27") (pin "2") (pinfunction "2_2") (pintype "input"))
      (node (ref "U3") (pin "7") (pinfunction "IO35_7") (pintype "unspecified"))
    )
    (net (code "25") (name "Net-(C9-Pad1)") (class "Default")
      (node (ref "C9") (pin "1") (pinfunction "1_1") (pintype "input"))
      (node (ref "R8") (pin "2") (pinfunction "2_2") (pintype "input"))
    )
    (net (code "26") (name "Net-(CN3-CC1)") (class "Default")
      (node (ref "CN3") (pin "A5") (pinfunction "CC1_A5") (pintype "input"))
      (node (ref "R4") (pin "2") (pinfunction "2_2") (pintype "input"))
    )
    (net (code "27") (name "Net-(CN3-CC2)") (class "Default")
      (node (ref "CN3") (pin "B5") (pinfunction "CC2_B5") (pintype "input"))
      (node (ref "R3") (pin "2") (pinfunction "2_2") (pintype "input"))
    )
    (net (code "28") (name "Net-(CN4-Pad1)") (class "Default")
      (node (ref "CN4") (pin "1") (pinfunction "1_1") (pintype "unspecified"))
      (node (ref "K2") (pin "3") (pinfunction "3_3") (pintype "unspecified"))
    )
    (net (code "29") (name "Net-(CN4-Pad2)") (class "Default")
      (node (ref "CN4") (pin "2") (pinfunction "2_2") (pintype "unspecified"))
      (node (ref "K2") (pin "2") (pinfunction "2_2") (pintype "unspecified"))
    )
    (net (code "30") (name "Net-(CN5-Pad1)") (class "Default")
      (node (ref "CN5") (pin "1") (pinfunction "1_1") (pintype "unspecified"))
      (node (ref "K3") (pin "3") (pinfunction "3_3") (pintype "unspecified"))
    )
    (net (code "31") (name "Net-(CN5-Pad2)") (class "Default")
      (node (ref "CN5") (pin "2") (pinfunction "2_2") (pintype "unspecified"))
      (node (ref "K3") (pin "2") (pinfunction "2_2") (pintype "unspecified"))
    )
    (net (code "32") (name "Net-(CN6-Pad1)") (class "Default")
      (node (ref "CN6") (pin "1") (pinfunction "1_1") (pintype "unspecified"))
      (node (ref "K4") (pin "3") (pinfunction "3_3") (pintype "unspecified"))
    )
    (net (code "33") (name "Net-(CN6-Pad2)") (class "Default")
      (node (ref "CN6") (pin "2") (pinfunction "2_2") (pintype "unspecified"))
      (node (ref "K4") (pin "2") (pinfunction "2_2") (pintype "unspecified"))
    )
    (net (code "34") (name "Net-(CN9-Pad1)") (class "Default")
      (node (ref "CN9") (pin "1") (pinfunction "1_1") (pintype "unspecified"))
      (node (ref "K1") (pin "3") (pinfunction "3_3") (pintype "unspecified"))
    )
    (net (code "35") (name "Net-(CN9-Pad2)") (class "Default")
      (node (ref "CN9") (pin "2") (pinfunction "2_2") (pintype "unspecified"))
      (node (ref "K1") (pin "2") (pinfunction "2_2") (pintype "unspecified"))
    )
    (net (code "36") (name "Net-(D3-A)") (class "Default")
      (node (ref "D3") (pin "2") (pinfunction "A_2") (pintype "unspecified"))
      (node (ref "LD1") (pin "2") (pinfunction "A_2") (pintype "input"))
      (node (ref "LD2") (pin "2") (pinfunction "A_2") (pintype "input"))
      (node (ref "Q2") (pin "1") (pinfunction "G_1") (pintype "unspecified"))
      (node (ref "R6") (pin "2") (pinfunction "2_2") (pintype "unspecified"))
      (node (ref "U6") (pin "4") (pinfunction "VCC_4") (pintype "unspecified"))
      (node (ref "U6") (pin "8") (pinfunction "CE_8") (pintype "unspecified"))
    )
    (net (code "37") (name "Net-(D4-A)") (class "Default")
      (node (ref "D4") (pin "2") (pinfunction "A_2") (pintype "unspecified"))
      (node (ref "K1") (pin "1") (pinfunction "1_1") (pintype "unspecified"))
      (node (ref "Q5") (pin "3") (pinfunction "C_3") (pintype "input"))
    )
    (net (code "38") (name "Net-(D5-A)") (class "Default")
      (node (ref "D5") (pin "2") (pinfunction "A_2") (pintype "unspecified"))
      (node (ref "K2") (pin "1") (pinfunction "1_1") (pintype "unspecified"))
      (node (ref "Q6") (pin "3") (pinfunction "C_3") (pintype "input"))
    )
    (net (code "39") (name "Net-(D6-A)") (class "Default")
      (node (ref "D6") (pin "2") (pinfunction "A_2") (pintype "unspecified"))
      (node (ref "K3") (pin "1") (pinfunction "1_1") (pintype "unspecified"))
      (node (ref "Q7") (pin "3") (pinfunction "C_3") (pintype "input"))
    )
    (net (code "40") (name "Net-(D7-A)") (class "Default")
      (node (ref "D7") (pin "2") (pinfunction "A_2") (pintype "unspecified"))
      (node (ref "K4") (pin "1") (pinfunction "1_1") (pintype "unspecified"))
      (node (ref "Q8") (pin "3") (pinfunction "C_3") (pintype "input"))
    )
    (net (code "41") (name "Net-(LD1-C)") (class "Default")
      (node (ref "LD1") (pin "1") (pinfunction "C_1") (pintype "input"))
      (node (ref "R5") (pin "2") (pinfunction "2_2") (pintype "input"))
    )
    (net (code "42") (name "Net-(LD2-C)") (class "Default")
      (node (ref "LD2") (pin "1") (pinfunction "C_1") (pintype "input"))
      (node (ref "R2") (pin "2") (pinfunction "2_2") (pintype "input"))
    )
    (net (code "43") (name "Net-(LD3-C)") (class "Default")
      (node (ref "LD3") (pin "1") (pinfunction "C_1") (pintype "input"))
      (node (ref "R42") (pin "1") (pinfunction "1_1") (pintype "input"))
    )
    (net (code "44") (name "Net-(Q3-B)") (class "Default")
      (node (ref "Q3") (pin "1") (pinfunction "B_1") (pintype "input"))
      (node (ref "R10") (pin "1") (pinfunction "1_1") (pintype "input"))
    )
    (net (code "45") (name "Net-(Q3-E)") (class "Default")
      (node (ref "Q3") (pin "2") (pinfunction "E_2") (pintype "input"))
      (node (ref "R11") (pin "2") (pinfunction "2_2") (pintype "input"))
      (node (ref "U4") (pin "14") (pinfunction "RTS#_14") (pintype "unspecified"))
    )
    (net (code "46") (name "Net-(Q4-B)") (class "Default")
      (node (ref "Q4") (pin "1") (pinfunction "B_1") (pintype "input"))
      (node (ref "R11") (pin "1") (pinfunction "1_1") (pintype "input"))
    )
    (net (code "47") (name "Net-(Q4-E)") (class "Default")
      (node (ref "Q4") (pin "2") (pinfunction "E_2") (pintype "input"))
      (node (ref "R10") (pin "2") (pinfunction "2_2") (pintype "input"))
      (node (ref "U4") (pin "13") (pinfunction "DTR#_13") (pintype "unspecified"))
    )
    (net (code "48") (name "Net-(Q5-B)") (class "Default")
      (node (ref "Q5") (pin "1") (pinfunction "B_1") (pintype "input"))
      (node (ref "R21") (pin "1") (pinfunction "1_1") (pintype "input"))
      (node (ref "R22") (pin "2") (pinfunction "2_2") (pintype "input"))
    )
    (net (code "49") (name "Net-(Q6-B)") (class "Default")
      (node (ref "Q6") (pin "1") (pinfunction "B_1") (pintype "input"))
      (node (ref "R23") (pin "1") (pinfunction "1_1") (pintype "input"))
      (node (ref "R24") (pin "2") (pinfunction "2_2") (pintype "input"))
    )
    (net (code "50") (name "Net-(Q7-B)") (class "Default")
      (node (ref "Q7") (pin "1") (pinfunction "B_1") (pintype "input"))
      (node (ref "R25") (pin "1") (pinfunction "1_1") (pintype "input"))
      (node (ref "R26") (pin "2") (pinfunction "2_2") (pintype "input"))
    )
    (net (code "51") (name "Net-(Q8-B)") (class "Default")
      (node (ref "Q8") (pin "1") (pinfunction "B_1") (pintype "input"))
      (node (ref "R27") (pin "1") (pinfunction "1_1") (pintype "input"))
      (node (ref "R28") (pin "2") (pinfunction "2_2") (pintype "input"))
    )
    (net (code "52") (name "Net-(R32-Pad2)") (class "Default")
      (node (ref "R32") (pin "2") (pinfunction "2_2") (pintype "input"))
      (node (ref "R33") (pin "2") (pinfunction "2_2") (pintype "input"))
    )
    (net (code "53") (name "Net-(TF1-CD{slash}DAT3)") (class "Default")
      (node (ref "R15") (pin "1") (pinfunction "1_1") (pintype "input"))
      (node (ref "TF1") (pin "2") (pinfunction "CD/DAT3_2") (pintype "unspecified"))
    )
    (net (code "54") (name "Net-(TF1-CLK)") (class "Default")
      (node (ref "R17") (pin "1") (pinfunction "1_1") (pintype "input"))
      (node (ref "TF1") (pin "5") (pinfunction "CLK_5") (pintype "unspecified"))
    )
    (net (code "55") (name "Net-(TF1-DAT0)") (class "Default")
      (node (ref "R20") (pin "1") (pinfunction "1_1") (pintype "input"))
      (node (ref "TF1") (pin "7") (pinfunction "DAT0_7") (pintype "unspecified"))
    )
    (net (code "56") (name "Net-(TF1-DAT1)") (class "Default")
      (node (ref "R19") (pin "1") (pinfunction "1_1") (pintype "input"))
      (node (ref "TF1") (pin "8") (pinfunction "DAT1_8") (pintype "unspecified"))
    )
    (net (code "57") (name "Net-(TF1-DAT2)") (class "Default")
      (node (ref "R14") (pin "1") (pinfunction "1_1") (pintype "input"))
      (node (ref "TF1") (pin "1") (pinfunction "DAT2_1") (pintype "unspecified"))
    )
    (net (code "58") (name "Net-(TF1-VDD)") (class "Default")
      (node (ref "C15") (pin "1") (pinfunction "1_1") (pintype "input"))
      (node (ref "FB1") (pin "2") (pinfunction "2_2") (pintype "unspecified"))
      (node (ref "TF1") (pin "4") (pinfunction "VDD_4") (pintype "unspecified"))
    )
    (net (code "59") (name "Net-(U6-CHRG#)") (class "Default")
      (node (ref "R2") (pin "1") (pinfunction "1_1") (pintype "input"))
      (node (ref "U6") (pin "7") (pinfunction "CHRG#_7") (pintype "unspecified"))
    )
    (net (code "60") (name "Net-(U6-PROG)") (class "Default")
      (node (ref "R7") (pin "1") (pinfunction "1_1") (pintype "input"))
      (node (ref "U6") (pin "2") (pinfunction "PROG_2") (pintype "unspecified"))
    )
    (net (code "61") (name "Net-(U6-STDBY#)") (class "Default")
      (node (ref "R5") (pin "1") (pinfunction "1_1") (pintype "input"))
      (node (ref "U6") (pin "6") (pinfunction "STDBY#_6") (pintype "unspecified"))
    )
    (net (code "62") (name "Net-(U7-FB)") (class "Default")
      (node (ref "C9") (pin "2") (pinfunction "2_2") (pintype "input"))
      (node (ref "R8") (pin "1") (pinfunction "1_1") (pintype "input"))
      (node (ref "R9") (pin "2") (pinfunction "2_2") (pintype "input"))
      (node (ref "U7") (pin "5") (pinfunction "FB_5") (pintype "input"))
    )
    (net (code "63") (name "Net-(U7-SW)") (class "Default")
      (node (ref "L1") (pin "1") (pinfunction "1_1") (pintype "unspecified"))
      (node (ref "U7") (pin "3") (pinfunction "SW_3") (pintype "input"))
    )
    (net (code "64") (name "Net-(U8-DI)") (class "Default")
      (node (ref "R30") (pin "1") (pinfunction "1_1") (pintype "input"))
      (node (ref "U8") (pin "4") (pinfunction "DI_4") (pintype "unspecified"))
    )
    (net (code "65") (name "Net-(U8-R0)") (class "Default")
      (node (ref "R29") (pin "1") (pinfunction "1_1") (pintype "input"))
      (node (ref "U8") (pin "1") (pinfunction "R0_1") (pintype "unspecified"))
    )
    (net (code "66") (name "Net-(U9-1Y)") (class "Default")
      (node (ref "CN8") (pin "1") (pinfunction "1_1") (pintype "unspecified"))
      (node (ref "U9") (pin "3") (pinfunction "1Y_3") (pintype "unspecified"))
    )
    (net (code "67") (name "Net-(U9-2Y)") (class "Default")
      (node (ref "CN8") (pin "3") (pinfunction "3_3") (pintype "unspecified"))
      (node (ref "U9") (pin "6") (pinfunction "2Y_6") (pintype "unspecified"))
    )
    (net (code "68") (name "Net-(U9-3Y)") (class "Default")
      (node (ref "CN8") (pin "5") (pinfunction "5_5") (pintype "unspecified"))
      (node (ref "U9") (pin "8") (pinfunction "3Y_8") (pintype "unspecified"))
    )
    (net (code "69") (name "Net-(U9-4Y)") (class "Default")
      (node (ref "CN8") (pin "7") (pinfunction "7_7") (pintype "unspecified"))
      (node (ref "U9") (pin "11") (pinfunction "4Y_11") (pintype "unspecified"))
    )
    (net (code "70") (name "Net-(U9-VCC)") (class "Default")
      (node (ref "C21") (pin "2") (pinfunction "2_2") (pintype "input"))
      (node (ref "C22") (pin "2") (pinfunction "2_2") (pintype "input"))
      (node (ref "R40") (pin "1") (pinfunction "1_1") (pintype "input"))
      (node (ref "R41") (pin "1") (pinfunction "1_1") (pintype "input"))
      (node (ref "U9") (pin "14") (pinfunction "VCC_14") (pintype "unspecified"))
    )
    (net (code "71") (name "RS485+") (class "Default")
      (node (ref "CN10") (pin "2") (pinfunction "2_2") (pintype "unspecified"))
      (node (ref "R33") (pin "1") (pinfunction "1_1") (pintype "input"))
      (node (ref "U8") (pin "6") (pinfunction "A_6") (pintype "unspecified"))
    )
    (net (code "72") (name "RS485-") (class "Default")
      (node (ref "CN10") (pin "1") (pinfunction "1_1") (pintype "unspecified"))
      (node (ref "R32") (pin "1") (pinfunction "1_1") (pintype "input"))
      (node (ref "U8") (pin "7") (pinfunction "B_7") (pintype "unspecified"))
    )
    (net (code "73") (name "RXD0") (class "Default")
      (node (ref "U3") (pin "34") (pinfunction "RXD0_34") (pintype "unspecified"))
      (node (ref "U4") (pin "2") (pinfunction "TXD_2") (pintype "unspecified"))
    )
    (net (code "74") (name "TXD0") (class "Default")
      (node (ref "U3") (pin "35") (pinfunction "TXD0_35") (pintype "unspecified"))
      (node (ref "U4") (pin "3") (pinfunction "RXD_3") (pintype "unspecified"))
    )
    (net (code "75") (name "USR_LED") (class "Default")
      (node (ref "R42") (pin "2") (pinfunction "2_2") (pintype "input"))
      (node (ref "U3") (pin "14") (pinfunction "IO12_14") (pintype "unspecified"))
    )
    (net (code "76") (name "VBAT") (class "Default")
      (node (ref "C5") (pin "2") (pinfunction "2_2") (pintype "input"))
      (node (ref "C6") (pin "2") (pinfunction "2_2") (pintype "input"))
      (node (ref "CN2") (pin "1") (pinfunction "1_1") (pintype "unspecified"))
      (node (ref "Q2") (pin "3") (pinfunction "D_3") (pintype "unspecified"))
      (node (ref "R36") (pin "2") (pinfunction "2_2") (pintype "input"))
      (node (ref "U6") (pin "5") (pinfunction "BAT_5") (pintype "unspecified"))
    )
    (net (code "77") (name "VBUS") (class "Default")
      (node (ref "CN3") (pin "A4") (pinfunction "VBUS_A4") (pintype "input"))
      (node (ref "CN3") (pin "A9") (pinfunction "VBUS_A9") (pintype "input"))
      (node (ref "CN3") (pin "B4") (pinfunction "VBUS_B4") (pintype "input"))
      (node (ref "CN3") (pin "B9") (pinfunction "VBUS_B9") (pintype "input"))
      (node (ref "Q1") (pin "3") (pinfunction "D_3") (pintype "unspecified"))
    )
    (net (code "78") (name "VDC") (class "Default")
      (node (ref "C7") (pin "2") (pinfunction "2_2") (pintype "input"))
      (node (ref "C8") (pin "2") (pinfunction "2_2") (pintype "input"))
      (node (ref "D3") (pin "1") (pinfunction "C_1") (pintype "unspecified"))
      (node (ref "Q2") (pin "2") (pinfunction "S_2") (pintype "unspecified"))
      (node (ref "U7") (pin "1") (pinfunction "EN_1") (pintype "input"))
    )
    (net (code "79") (name "VDD") (class "Default")
      (node (ref "C10") (pin "2") (pinfunction "2_2") (pintype "input"))
      (node (ref "C11") (pin "2") (pinfunction "2_2") (pintype "input"))
      (node (ref "C12") (pin "1") (pinfunction "1_1") (pintype "input"))
      (node (ref "C13") (pin "2") (pinfunction "2_2") (pintype "input"))
      (node (ref "C16") (pin "1") (pinfunction "1_1") (pintype "input"))
      (node (ref "C23") (pin "1") (pinfunction "1_1") (pintype "input"))
      (node (ref "CN8") (pin "6") (pinfunction "6_6") (pintype "unspecified"))
      (node (ref "FB1") (pin "1") (pinfunction "1_1") (pintype "unspecified"))
      (node (ref "L1") (pin "2") (pinfunction "2_2") (pintype "unspecified"))
      (node (ref "LD3") (pin "2") (pinfunction "A_2") (pintype "input"))
      (node (ref "R12") (pin "2") (pinfunction "2_2") (pintype "input"))
      (node (ref "R13") (pin "2") (pinfunction "2_2") (pintype "input"))
      (node (ref "R14") (pin "2") (pinfunction "2_2") (pintype "input"))
      (node (ref "R15") (pin "2") (pinfunction "2_2") (pintype "input"))
      (node (ref "R16") (pin "2") (pinfunction "2_2") (pintype "input"))
      (node (ref "R18") (pin "2") (pinfunction "2_2") (pintype "input"))
      (node (ref "R19") (pin "2") (pinfunction "2_2") (pintype "input"))
      (node (ref "R38") (pin "2") (pinfunction "2_2") (pintype "input"))
      (node (ref "R39") (pin "2") (pinfunction "2_2") (pintype "input"))
      (node (ref "R41") (pin "2") (pinfunction "2_2") (pintype "input"))
      (node (ref "R43") (pin "2") (pinfunction "2_2") (pintype "input"))
      (node (ref "U10") (pin "3") (pinfunction "VDD_3") (pintype "input"))
      (node (ref "U3") (pin "2") (pinfunction "3V3_2") (pintype "unspecified"))
      (node (ref "U4") (pin "16") (pinfunction "VCC_16") (pintype "unspecified"))
      (node (ref "U4") (pin "4") (pinfunction "V3_4") (pintype "unspecified"))
      (node (ref "U8") (pin "8") (pinfunction "VCC_8") (pintype "unspecified"))
    )
    (net (code "80") (name "VEXT") (class "Default")
      (node (ref "C1") (pin "1") (pinfunction "1_1") (pintype "input"))
      (node (ref "C2") (pin "1") (pinfunction "1_1") (pintype "input"))
      (node (ref "C3") (pin "2") (pinfunction "2_2") (pintype "input"))
      (node (ref "C4") (pin "2") (pinfunction "2_2") (pintype "input"))
      (node (ref "CN8") (pin "2") (pinfunction "2_2") (pintype "unspecified"))
      (node (ref "D1") (pin "1") (pinfunction "C_1") (pintype "unspecified"))
      (node (ref "D2") (pin "1") (pinfunction "1_1") (pintype "unspecified"))
      (node (ref "D4") (pin "1") (pinfunction "C_1") (pintype "unspecified"))
      (node (ref "D5") (pin "1") (pinfunction "C_1") (pintype "unspecified"))
      (node (ref "D6") (pin "1") (pinfunction "C_1") (pintype "unspecified"))
      (node (ref "D7") (pin "1") (pinfunction "C_1") (pintype "unspecified"))
      (node (ref "K1") (pin "4") (pinfunction "4_4") (pintype "unspecified"))
      (node (ref "K2") (pin "4") (pinfunction "4_4") (pintype "unspecified"))
      (node (ref "K3") (pin "4") (pinfunction "4_4") (pintype "unspecified"))
      (node (ref "K4") (pin "4") (pinfunction "4_4") (pintype "unspecified"))
      (node (ref "Q1") (pin "2") (pinfunction "S_2") (pintype "unspecified"))
      (node (ref "R34") (pin "1") (pinfunction "1_1") (pintype "input"))
      (node (ref "R40") (pin "2") (pinfunction "2_2") (pintype "input"))
      (node (ref "R6") (pin "1") (pinfunction "1_1") (pintype "unspecified"))
    )
    (net (code "81") (name "V_EXT") (class "Default")
      (node (ref "CN1") (pin "1") (pinfunction "1_1") (pintype "unspecified"))
      (node (ref "D1") (pin "2") (pinfunction "A_2") (pintype "unspecified"))
      (node (ref "DC1") (pin "1") (pinfunction "4_1") (pintype "input"))
      (node (ref "Q1") (pin "1") (pinfunction "G_1") (pintype "unspecified"))
      (node (ref "R1") (pin "2") (pinfunction "2_2") (pintype "input"))
    )
    (net (code "82") (name "unconnected-(CN3-SBUS1-PadA8)") (class "Default")
      (node (ref "CN3") (pin "A8") (pinfunction "SBUS1_A8") (pintype "input+no_connect"))
    )
    (net (code "83") (name "unconnected-(CN3-SBUS2-PadB8)") (class "Default")
      (node (ref "CN3") (pin "B8") (pinfunction "SBUS2_B8") (pintype "input+no_connect"))
    )
    (net (code "84") (name "unconnected-(TF1-CD-Pad9)") (class "Default")
      (node (ref "TF1") (pin "9") (pinfunction "CD_9") (pintype "unspecified+no_connect"))
    )
    (net (code "85") (name "unconnected-(U3-CLK-Pad20)") (class "Default")
      (node (ref "U3") (pin "20") (pinfunction "CLK_20") (pintype "unspecified+no_connect"))
    )
    (net (code "86") (name "unconnected-(U3-CMD-Pad19)") (class "Default")
      (node (ref "U3") (pin "19") (pinfunction "CMD_19") (pintype "unspecified+no_connect"))
    )
    (net (code "87") (name "unconnected-(U3-IO27-Pad12)") (class "Default")
      (node (ref "U3") (pin "12") (pinfunction "IO27_12") (pintype "unspecified+no_connect"))
    )
    (net (code "88") (name "unconnected-(U3-NC-Pad32)") (class "Default")
      (node (ref "U3") (pin "32") (pinfunction "NC_32") (pintype "unspecified+no_connect"))
    )
    (net (code "89") (name "unconnected-(U3-SD0-Pad21)") (class "Default")
      (node (ref "U3") (pin "21") (pinfunction "SD0_21") (pintype "unspecified+no_connect"))
    )
    (net (code "90") (name "unconnected-(U3-SD1-Pad22)") (class "Default")
      (node (ref "U3") (pin "22") (pinfunction "SD1_22") (pintype "unspecified+no_connect"))
    )
    (net (code "91") (name "unconnected-(U3-SD2-Pad17)") (class "Default")
      (node (ref "U3") (pin "17") (pinfunction "SD2_17") (pintype "unspecified+no_connect"))
    )
    (net (code "92") (name "unconnected-(U3-SD3-Pad18)") (class "Default")
      (node (ref "U3") (pin "18") (pinfunction "SD3_18") (pintype "unspecified+no_connect"))
    )
    (net (code "93") (name "unconnected-(U3-SENSOR_VN-Pad5)") (class "Default")
      (node (ref "U3") (pin "5") (pinfunction "SENSOR_VN_5") (pintype "unspecified+no_connect"))
    )
    (net (code "94") (name "unconnected-(U3-SENSOR_VP-Pad4)") (class "Default")
      (node (ref "U3") (pin "4") (pinfunction "SENSOR_VP_4") (pintype "unspecified+no_connect"))
    )
    (net (code "95") (name "unconnected-(U4-CTS#-Pad9)") (class "Default")
      (node (ref "U4") (pin "9") (pinfunction "CTS#_9") (pintype "unspecified+no_connect"))
    )
    (net (code "96") (name "unconnected-(U4-DCD#-Pad12)") (class "Default")
      (node (ref "U4") (pin "12") (pinfunction "DCD#_12") (pintype "unspecified+no_connect"))
    )
    (net (code "97") (name "unconnected-(U4-DSR#-Pad10)") (class "Default")
      (node (ref "U4") (pin "10") (pinfunction "DSR#_10") (pintype "unspecified+no_connect"))
    )
    (net (code "98") (name "unconnected-(U4-NC.-Pad7)") (class "Default")
      (node (ref "U4") (pin "7") (pinfunction "NC._7") (pintype "unspecified+no_connect"))
    )
    (net (code "99") (name "unconnected-(U4-OUT#-Pad8)") (class "Default")
      (node (ref "U4") (pin "8") (pinfunction "OUT#_8") (pintype "unspecified+no_connect"))
    )
    (net (code "100") (name "unconnected-(U4-R232-Pad15)") (class "Default")
      (node (ref "U4") (pin "15") (pinfunction "R232_15") (pintype "unspecified+no_connect"))
    )
    (net (code "101") (name "unconnected-(U4-RI#-Pad11)") (class "Default")
      (node (ref "U4") (pin "11") (pinfunction "RI#_11") (pintype "unspecified+no_connect"))
    )
    (net (code "102") (name "unconnected-(U7-VIN-Pad4)") (class "Default")
      (node (ref "U7") (pin "4") (pinfunction "VIN_4") (pintype "input"))
    )
  )
)
